# ArduinoUnoShield.net
KiCad netlist of a schematic drawn in Altium Designer
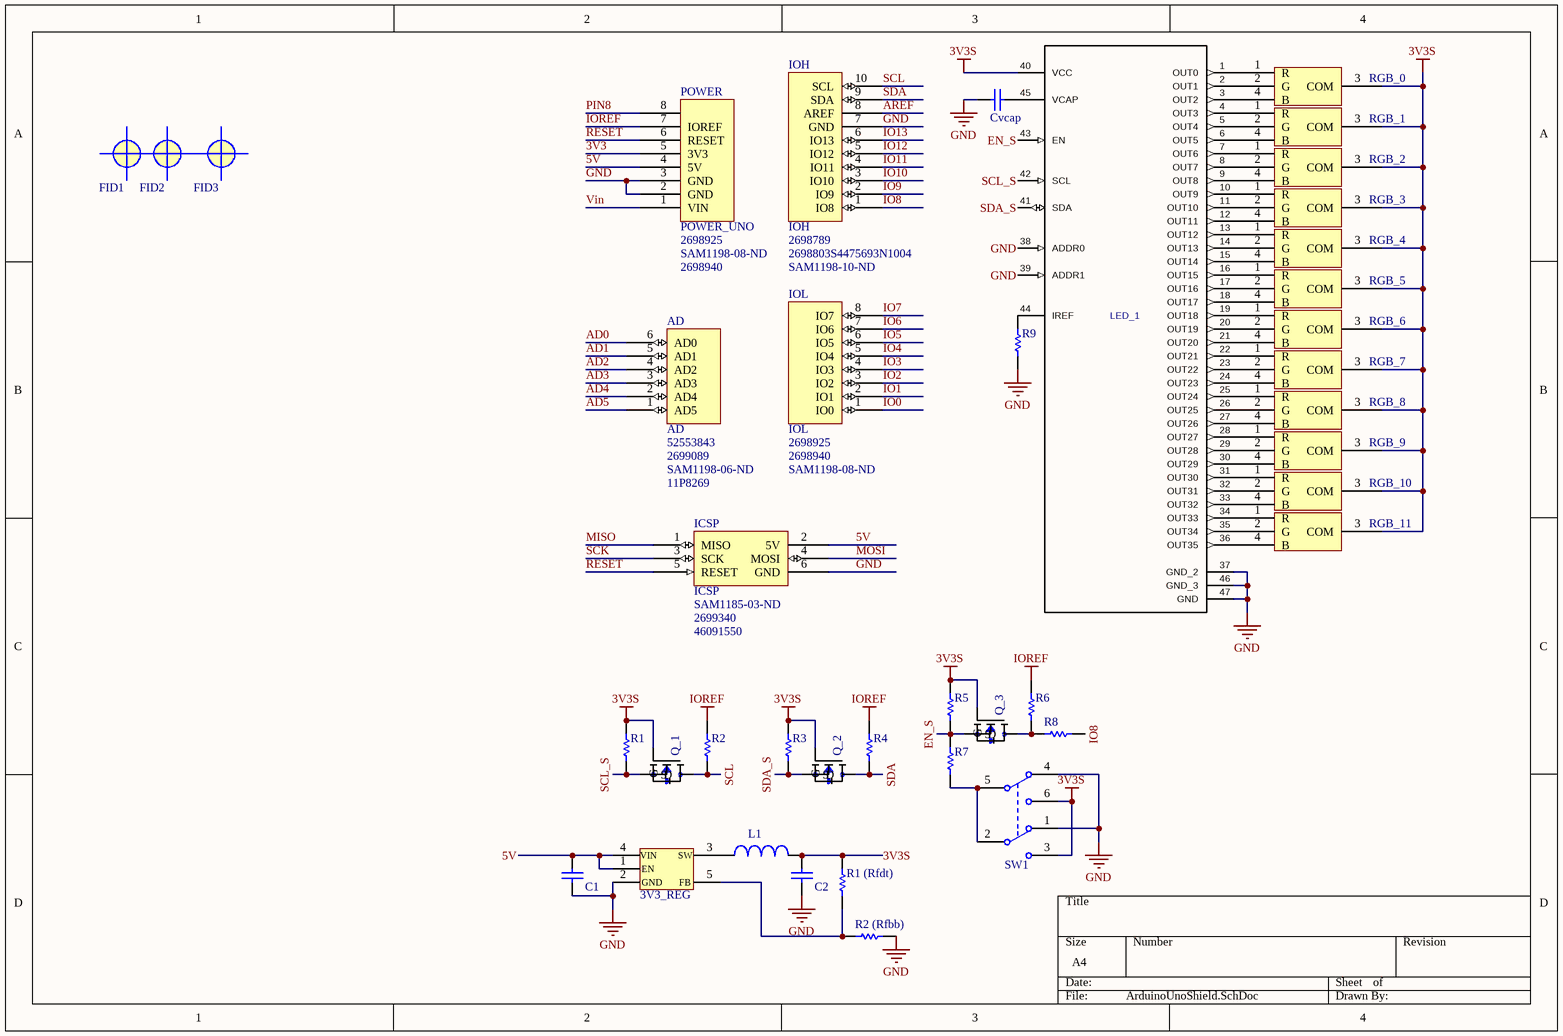
[diagram p0: ArduinoUnoShield.SchDoc]

(export (version "E")
  (design (tool "Eeschema 10.0.6"))
  (components
    (comp (ref "3V3_REG")
      (value "TLV62568DBVR")
      (footprint "*SOT95P280X145-5N")
      (libsource (lib "TLV62568DBVR") (part "TLV62568DBVR"))
    )
    (comp (ref "AD")
      (value "AD")
      (footprint "Header 6x1 8.5mm")
      (fields
        (field (name "SUPPLIER PART NUMBER 1") "52553843")
        (field (name "SUPPLIER PART NUMBER 2") "2699089")
        (field (name "SUPPLIER PART NUMBER 3") "SAM1198-06-ND")
        (field (name "SUPPLIER PART NUMBER 4") "11P8269")
      )
      (libsource (lib "Header") (part "AD"))
    )
    (comp (ref "C1")
      (value "4.7uF, 10%")
      (footprint "0805")
      (description "4.7uF, 10%, 10V")
      (fields (field (name "GFUPARTNO") "CL21A475KPFNNNE"))
      (libsource (lib "AltiumGFU64") (part "Cap"))
    )
    (comp (ref "C2")
      (value "1uF, 5%")
      (footprint "0805_CAP_HD")
      (description "1uF, 5%, 6.3V")
      (fields (field (name "GFUPARTNO") "08056D226MAT2A"))
      (libsource (lib "AltiumGFU64") (part "Cap"))
    )
    (comp (ref "Cvcap")
      (value "22uF, 20%")
      (footprint "0805_CAP_HD")
      (description "22uF, 20%, 6.3V")
      (fields (field (name "GFUPARTNO") "08056D226MAT2A"))
      (libsource (lib "AltiumGFU64") (part "Cap"))
    )
    (comp (ref "FID1")
      (value "FIDUCIAL")
      (footprint "FIDUCIAL (50MIL ROUND)")
      (description "FIDUCIAL (50MIL ROUND)")
      (libsource (lib "AltiumGFU64") (part "FIDUCIAL (ROUND)"))
    )
    (comp (ref "FID2")
      (value "FIDUCIAL")
      (footprint "FIDUCIAL (50MIL ROUND)")
      (description "FIDUCIAL (50MIL ROUND)")
      (libsource (lib "AltiumGFU64") (part "FIDUCIAL (ROUND)"))
    )
    (comp (ref "FID3")
      (value "FIDUCIAL")
      (footprint "FIDUCIAL (50MIL ROUND)")
      (description "FIDUCIAL (50MIL ROUND)")
      (libsource (lib "AltiumGFU64") (part "FIDUCIAL (ROUND)"))
    )
    (comp (ref "ICSP")
      (value "ICSP")
      (footprint "ICSP")
      (fields
        (field (name "SUPPLIER PART NUMBER 1") "SAM1185-03-ND")
        (field (name "SUPPLIER PART NUMBER 2") "2699340")
        (field (name "SUPPLIER PART NUMBER 3") "46091550")
      )
      (libsource (lib "Header") (part "ICSP"))
    )
    (comp (ref "IOH")
      (value "IOH")
      (footprint "Header 10x1 8.5mm")
      (fields
        (field (name "SUPPLIER PART NUMBER 1") "2698789")
        (field (name "SUPPLIER PART NUMBER 2") "2698803S4475693N1004")
        (field (name "SUPPLIER PART NUMBER 3") "SAM1198-10-ND")
      )
      (libsource (lib "Header") (part "IOH"))
    )
    (comp (ref "IOL")
      (value "IOL")
      (footprint "Header 8x1 8.5mm")
      (fields
        (field (name "SUPPLIER PART NUMBER 1") "2698925")
        (field (name "SUPPLIER PART NUMBER 2") "2698940")
        (field (name "SUPPLIER PART NUMBER 3") "SAM1198-08-ND")
      )
      (libsource (lib "Header") (part "IOL"))
    )
    (comp (ref "L1")
      (value "SDR0403-2R2ML")
      (footprint "*SDR0403")
      (description "2.2µH Unshielded Wirewound Inductor 2.6A 47mOhm Max Nonstandard")
      (fields (field (name "MF") "Bourns"))
      (libsource (lib "SDR0403-2R2ML") (part "SDR0403-2R2ML"))
    )
    (comp (ref "LED_1")
      (value "LP5036RJVR")
      (footprint "RJV0046A")
      (fields (field (name "MANUFACTURER") "Texas Instruments"))
      (libsource (lib "LP5036") (part "LP5036RJVR"))
    )
    (comp (ref "POWER")
      (value "POWER_UNO")
      (footprint "Header 8x1 8.5mm v2")
      (fields
        (field (name "SUPPLIER PART NUMBER 1") "2698925")
        (field (name "SUPPLIER PART NUMBER 2") "SAM1198-08-ND")
        (field (name "SUPPLIER PART NUMBER 3") "2698940")
      )
      (libsource (lib "Header") (part "POWER_UNO"))
    )
    (comp (ref "Q_1")
      (value "BSS138")
      (footprint "*BSS138_BSS138(Primary)")
      (description "N-Channel 50V 220mA _Ta_ 360mW _Ta_ Surface Mount Die")
      (fields (field (name "MF") "MICROSS/On Semiconductor"))
      (libsource (lib "BSS138") (part "BSS138"))
    )
    (comp (ref "Q_2")
      (value "BSS138")
      (footprint "*BSS138_BSS138(Primary)")
      (description "N-Channel 50V 220mA _Ta_ 360mW _Ta_ Surface Mount Die")
      (fields (field (name "MF") "MICROSS/On Semiconductor"))
      (libsource (lib "BSS138") (part "BSS138"))
    )
    (comp (ref "Q_3")
      (value "BSS138")
      (footprint "*BSS138_BSS138(Primary)")
      (description "N-Channel 50V 220mA _Ta_ 360mW _Ta_ Surface Mount Die")
      (fields (field (name "MF") "MICROSS/On Semiconductor"))
      (libsource (lib "BSS138") (part "BSS138"))
    )
    (comp (ref "R1")
      (value "4.7K, 5%")
      (footprint "0805")
      (description "RES 4.7K OHM 1/8W 5% 0805 SMD")
      (fields (field (name "GFUPARTNO") "RMCF0805JT4K70"))
      (libsource (lib "AltiumGFU64") (part "ResBasic"))
    )
    (comp (ref "R1 (Rfdt)")
      (value "R-NP")
      (footprint "0805_RES_HD")
      (description "NO PLACE RESISTOR")
      (fields (field (name "GFUPARTNO") "R-NP 0805"))
      (libsource (lib "AltiumGFU64") (part "ResBasic No Place"))
    )
    (comp (ref "R2")
      (value "4.7K, 5%")
      (footprint "0805")
      (description "RES 4.7K OHM 1/8W 5% 0805 SMD")
      (fields (field (name "GFUPARTNO") "RMCF0805JT4K70"))
      (libsource (lib "AltiumGFU64") (part "ResBasic"))
    )
    (comp (ref "R2 (Rfbb)")
      (value "R-NP")
      (footprint "0805_RES_HD")
      (description "NO PLACE RESISTOR")
      (fields (field (name "GFUPARTNO") "R-NP 0805"))
      (libsource (lib "AltiumGFU64") (part "ResBasic No Place"))
    )
    (comp (ref "R3")
      (value "4.7K, 5%")
      (footprint "0805")
      (description "RES 4.7K OHM 1/8W 5% 0805 SMD")
      (fields (field (name "GFUPARTNO") "RMCF0805JT4K70"))
      (libsource (lib "AltiumGFU64") (part "ResBasic"))
    )
    (comp (ref "R4")
      (value "4.7K, 5%")
      (footprint "0805")
      (description "RES 4.7K OHM 1/8W 5% 0805 SMD")
      (fields (field (name "GFUPARTNO") "RMCF0805JT4K70"))
      (libsource (lib "AltiumGFU64") (part "ResBasic"))
    )
    (comp (ref "R5")
      (value "4.7K, 5%")
      (footprint "0805")
      (description "RES 4.7K OHM 1/8W 5% 0805 SMD")
      (fields (field (name "GFUPARTNO") "RMCF0805JT4K70"))
      (libsource (lib "AltiumGFU64") (part "ResBasic"))
    )
    (comp (ref "R6")
      (value "4.7K, 5%")
      (footprint "0805")
      (description "RES 4.7K OHM 1/8W 5% 0805 SMD")
      (fields (field (name "GFUPARTNO") "RMCF0805JT4K70"))
      (libsource (lib "AltiumGFU64") (part "ResBasic"))
    )
    (comp (ref "R7")
      (value "0, 5%")
      (footprint "0603_RES_HD")
      (description "RES 0.0 OHM 1/10W 5% 0603 SMD")
      (fields (field (name "GFUPARTNO") "CRCW06030000Z0EA"))
      (libsource (lib "AltiumGFU64") (part "ResBasic"))
    )
    (comp (ref "R8")
      (value "0, 5%")
      (footprint "0603_RES_HD")
      (description "RES 0.0 OHM 1/10W 5% 0603 SMD")
      (fields (field (name "GFUPARTNO") "CRCW06030000Z0EA"))
      (libsource (lib "AltiumGFU64") (part "ResBasic"))
    )
    (comp (ref "R9")
      (value "4.7K, 5%")
      (footprint "0805")
      (description "RES 4.7K OHM 1/8W 5% 0805 SMD")
      (fields (field (name "GFUPARTNO") "RMCF0805JT4K70"))
      (libsource (lib "AltiumGFU64") (part "ResBasic"))
    )
    (comp (ref "RGB_0")
      (value "RGB LED")
      (footprint "PCBComponent_1")
      (libsource (lib "RGB_LED") (part "RGB LED"))
    )
    (comp (ref "RGB_1")
      (value "RGB LED")
      (footprint "PCBComponent_1")
      (libsource (lib "RGB_LED") (part "RGB LED"))
    )
    (comp (ref "RGB_2")
      (value "RGB LED")
      (footprint "PCBComponent_1")
      (libsource (lib "RGB_LED") (part "RGB LED"))
    )
    (comp (ref "RGB_3")
      (value "RGB LED")
      (footprint "PCBComponent_1")
      (libsource (lib "RGB_LED") (part "RGB LED"))
    )
    (comp (ref "RGB_4")
      (value "RGB LED")
      (footprint "PCBComponent_1")
      (libsource (lib "RGB_LED") (part "RGB LED"))
    )
    (comp (ref "RGB_5")
      (value "RGB LED")
      (footprint "PCBComponent_1")
      (libsource (lib "RGB_LED") (part "RGB LED"))
    )
    (comp (ref "RGB_6")
      (value "RGB LED")
      (footprint "PCBComponent_1")
      (libsource (lib "RGB_LED") (part "RGB LED"))
    )
    (comp (ref "RGB_7")
      (value "RGB LED")
      (footprint "PCBComponent_1")
      (libsource (lib "RGB_LED") (part "RGB LED"))
    )
    (comp (ref "RGB_8")
      (value "RGB LED")
      (footprint "PCBComponent_1")
      (libsource (lib "RGB_LED") (part "RGB LED"))
    )
    (comp (ref "RGB_9")
      (value "RGB LED")
      (footprint "PCBComponent_1")
      (libsource (lib "RGB_LED") (part "RGB LED"))
    )
    (comp (ref "RGB_10")
      (value "RGB LED")
      (footprint "PCBComponent_1")
      (libsource (lib "RGB_LED") (part "RGB LED"))
    )
    (comp (ref "RGB_11")
      (value "RGB LED")
      (footprint "PCBComponent_1")
      (libsource (lib "RGB_LED") (part "RGB LED"))
    )
    (comp (ref "SW1")
      (value "JS202011SCQN")
      (footprint "JS202011SCQN")
      (description "SWITCH SLIDE DPDT 6VDC 0.3A SMT")
      (libsource (lib "AltiumGFU64") (part "JS202011SCQN"))
    )
  )
  (nets
    (net (code "1") (name "/3V3") (class "Default")
      (node (ref "POWER") (pin "5") (pinfunction "3V3_5") (pintype "power_in"))
    )
    (net (code "2") (name "/5V") (class "Default")
      (node (ref "3V3_REG") (pin "1") (pinfunction "1_1") (pintype "passive"))
      (node (ref "3V3_REG") (pin "4") (pinfunction "4_4") (pintype "passive"))
      (node (ref "C1") (pin "2") (pinfunction "2_2") (pintype "passive"))
      (node (ref "ICSP") (pin "2") (pinfunction "5V_2") (pintype "power_in"))
      (node (ref "POWER") (pin "4") (pinfunction "5V_4") (pintype "power_in"))
    )
    (net (code "3") (name "/AD0") (class "Default")
      (node (ref "AD") (pin "6") (pinfunction "AD0_6") (pintype "bidirectional"))
    )
    (net (code "4") (name "/AD1") (class "Default")
      (node (ref "AD") (pin "5") (pinfunction "AD1_5") (pintype "bidirectional"))
    )
    (net (code "5") (name "/AD2") (class "Default")
      (node (ref "AD") (pin "4") (pinfunction "AD2_4") (pintype "bidirectional"))
    )
    (net (code "6") (name "/AD3") (class "Default")
      (node (ref "AD") (pin "3") (pinfunction "AD3_3") (pintype "bidirectional"))
    )
    (net (code "7") (name "/AD4") (class "Default")
      (node (ref "AD") (pin "2") (pinfunction "AD4_2") (pintype "bidirectional"))
    )
    (net (code "8") (name "/AD5") (class "Default")
      (node (ref "AD") (pin "1") (pinfunction "AD5_1") (pintype "bidirectional"))
    )
    (net (code "9") (name "/AREF") (class "Default")
      (node (ref "IOH") (pin "8") (pinfunction "AREF_8") (pintype "passive"))
    )
    (net (code "10") (name "/EN_S") (class "Default")
      (node (ref "LED_1") (pin "43") (pinfunction "EN_43") (pintype "input"))
      (node (ref "Q_3") (pin "S") (pinfunction "S_S") (pintype "passive"))
      (node (ref "R5") (pin "1") (pinfunction "1_1") (pintype "passive"))
      (node (ref "R7") (pin "2") (pinfunction "2_2") (pintype "passive"))
    )
    (net (code "11") (name "/IO0") (class "Default")
      (node (ref "IOL") (pin "1") (pinfunction "IO0_1") (pintype "bidirectional"))
    )
    (net (code "12") (name "/IO1") (class "Default")
      (node (ref "IOL") (pin "2") (pinfunction "IO1_2") (pintype "bidirectional"))
    )
    (net (code "13") (name "/IO2") (class "Default")
      (node (ref "IOL") (pin "3") (pinfunction "IO2_3") (pintype "bidirectional"))
    )
    (net (code "14") (name "/IO3") (class "Default")
      (node (ref "IOL") (pin "4") (pinfunction "IO3_4") (pintype "bidirectional"))
    )
    (net (code "15") (name "/IO4") (class "Default")
      (node (ref "IOL") (pin "5") (pinfunction "IO4_5") (pintype "bidirectional"))
    )
    (net (code "16") (name "/IO5") (class "Default")
      (node (ref "IOL") (pin "6") (pinfunction "IO5_6") (pintype "bidirectional"))
    )
    (net (code "17") (name "/IO6") (class "Default")
      (node (ref "IOL") (pin "7") (pinfunction "IO6_7") (pintype "bidirectional"))
    )
    (net (code "18") (name "/IO7") (class "Default")
      (node (ref "IOL") (pin "8") (pinfunction "IO7_8") (pintype "bidirectional"))
    )
    (net (code "19") (name "/IO8") (class "Default")
      (node (ref "IOH") (pin "1") (pinfunction "IO8_1") (pintype "bidirectional"))
      (node (ref "R8") (pin "1") (pinfunction "1_1") (pintype "passive"))
    )
    (net (code "20") (name "/IO9") (class "Default")
      (node (ref "IOH") (pin "2") (pinfunction "IO9_2") (pintype "bidirectional"))
    )
    (net (code "21") (name "/IO10") (class "Default")
      (node (ref "IOH") (pin "3") (pinfunction "IO10_3") (pintype "bidirectional"))
    )
    (net (code "22") (name "/IO11") (class "Default")
      (node (ref "IOH") (pin "4") (pinfunction "IO11_4") (pintype "bidirectional"))
    )
    (net (code "23") (name "/IO12") (class "Default")
      (node (ref "IOH") (pin "5") (pinfunction "IO12_5") (pintype "bidirectional"))
    )
    (net (code "24") (name "/IO13") (class "Default")
      (node (ref "IOH") (pin "6") (pinfunction "IO13_6") (pintype "bidirectional"))
    )
    (net (code "25") (name "/MISO") (class "Default")
      (node (ref "ICSP") (pin "1") (pinfunction "MISO_1") (pintype "bidirectional"))
    )
    (net (code "26") (name "/MOSI") (class "Default")
      (node (ref "ICSP") (pin "4") (pinfunction "MOSI_4") (pintype "bidirectional"))
    )
    (net (code "27") (name "/PIN8") (class "Default") (node (ref "POWER") (pin "8") (pintype "passive")))
    (net (code "28") (name "/RESET") (class "Default")
      (node (ref "ICSP") (pin "5") (pinfunction "RESET_5") (pintype "input"))
      (node (ref "POWER") (pin "6") (pinfunction "RESET_6") (pintype "passive"))
    )
    (net (code "29") (name "/SCK") (class "Default")
      (node (ref "ICSP") (pin "3") (pinfunction "SCK_3") (pintype "bidirectional"))
    )
    (net (code "30") (name "/SCL") (class "Default")
      (node (ref "IOH") (pin "10") (pinfunction "SCL_10") (pintype "bidirectional"))
      (node (ref "Q_1") (pin "D") (pinfunction "D_D") (pintype "passive"))
      (node (ref "R2") (pin "1") (pinfunction "1_1") (pintype "passive"))
    )
    (net (code "31") (name "/SCL_S") (class "Default")
      (node (ref "LED_1") (pin "42") (pinfunction "SCL_42") (pintype "input"))
      (node (ref "Q_1") (pin "S") (pinfunction "S_S") (pintype "passive"))
      (node (ref "R1") (pin "1") (pinfunction "1_1") (pintype "passive"))
    )
    (net (code "32") (name "/SDA") (class "Default")
      (node (ref "IOH") (pin "9") (pinfunction "SDA_9") (pintype "bidirectional"))
      (node (ref "Q_2") (pin "D") (pinfunction "D_D") (pintype "passive"))
      (node (ref "R4") (pin "1") (pinfunction "1_1") (pintype "passive"))
    )
    (net (code "33") (name "/SDA_S") (class "Default")
      (node (ref "LED_1") (pin "41") (pinfunction "SDA_41") (pintype "bidirectional"))
      (node (ref "Q_2") (pin "S") (pinfunction "S_S") (pintype "passive"))
      (node (ref "R3") (pin "1") (pinfunction "1_1") (pintype "passive"))
    )
    (net (code "34") (name "/Vin") (class "Default")
      (node (ref "POWER") (pin "1") (pinfunction "VIN_1") (pintype "power_in"))
    )
    (net (code "35") (name "3V3S") (class "Default")
      (node (ref "C2") (pin "2") (pinfunction "2_2") (pintype "passive"))
      (node (ref "L1") (pin "2") (pinfunction "2_2") (pintype "passive"))
      (node (ref "LED_1") (pin "40") (pinfunction "VCC_40") (pintype "power_in"))
      (node (ref "Q_1") (pin "G") (pinfunction "G_G") (pintype "passive"))
      (node (ref "Q_2") (pin "G") (pinfunction "G_G") (pintype "passive"))
      (node (ref "Q_3") (pin "G") (pinfunction "G_G") (pintype "passive"))
      (node (ref "R1") (pin "2") (pinfunction "2_2") (pintype "passive"))
      (node (ref "R1 (Rfdt)") (pin "2") (pinfunction "2_2") (pintype "passive"))
      (node (ref "R3") (pin "2") (pinfunction "2_2") (pintype "passive"))
      (node (ref "R5") (pin "2") (pinfunction "2_2") (pintype "passive"))
      (node (ref "RGB_0") (pin "3") (pinfunction "COM_3") (pintype "passive"))
      (node (ref "RGB_1") (pin "3") (pinfunction "COM_3") (pintype "passive"))
      (node (ref "RGB_10") (pin "3") (pinfunction "COM_3") (pintype "passive"))
      (node (ref "RGB_11") (pin "3") (pinfunction "COM_3") (pintype "passive"))
      (node (ref "RGB_2") (pin "3") (pinfunction "COM_3") (pintype "passive"))
      (node (ref "RGB_3") (pin "3") (pinfunction "COM_3") (pintype "passive"))
      (node (ref "RGB_4") (pin "3") (pinfunction "COM_3") (pintype "passive"))
      (node (ref "RGB_5") (pin "3") (pinfunction "COM_3") (pintype "passive"))
      (node (ref "RGB_6") (pin "3") (pinfunction "COM_3") (pintype "passive"))
      (node (ref "RGB_7") (pin "3") (pinfunction "COM_3") (pintype "passive"))
      (node (ref "RGB_8") (pin "3") (pinfunction "COM_3") (pintype "passive"))
      (node (ref "RGB_9") (pin "3") (pinfunction "COM_3") (pintype "passive"))
      (node (ref "SW1") (pin "3") (pinfunction "NO2_3") (pintype "passive"))
      (node (ref "SW1") (pin "6") (pinfunction "NC1_6") (pintype "passive"))
    )
    (net (code "36") (name "GND") (class "Default")
      (node (ref "3V3_REG") (pin "2") (pinfunction "2_2") (pintype "passive"))
      (node (ref "C1") (pin "1") (pinfunction "1_1") (pintype "passive"))
      (node (ref "C2") (pin "1") (pinfunction "1_1") (pintype "passive"))
      (node (ref "Cvcap") (pin "2") (pinfunction "2_2") (pintype "passive"))
      (node (ref "ICSP") (pin "6") (pinfunction "GND_6") (pintype "power_in"))
      (node (ref "IOH") (pin "7") (pinfunction "GND_7") (pintype "power_in"))
      (node (ref "LED_1") (pin "37") (pinfunction "GND_2_37") (pintype "power_in"))
      (node (ref "LED_1") (pin "38") (pinfunction "ADDR0_38") (pintype "input"))
      (node (ref "LED_1") (pin "39") (pinfunction "ADDR1_39") (pintype "input"))
      (node (ref "LED_1") (pin "46") (pinfunction "GND_3_46") (pintype "power_in"))
      (node (ref "LED_1") (pin "47") (pinfunction "GND_47") (pintype "power_in"))
      (node (ref "POWER") (pin "2") (pinfunction "GND_2") (pintype "power_in"))
      (node (ref "POWER") (pin "3") (pinfunction "GND_3") (pintype "power_in"))
      (node (ref "R2 (Rfbb)") (pin "2") (pinfunction "2_2") (pintype "passive"))
      (node (ref "R9") (pin "1") (pinfunction "1_1") (pintype "passive"))
      (node (ref "SW1") (pin "1") (pinfunction "NC2_1") (pintype "passive"))
      (node (ref "SW1") (pin "4") (pinfunction "NO1_4") (pintype "passive"))
    )
    (net (code "37") (name "IOREF") (class "Default")
      (node (ref "POWER") (pin "7") (pinfunction "IOREF_7") (pintype "power_in"))
      (node (ref "R2") (pin "2") (pinfunction "2_2") (pintype "passive"))
      (node (ref "R4") (pin "2") (pinfunction "2_2") (pintype "passive"))
      (node (ref "R6") (pin "2") (pinfunction "2_2") (pintype "passive"))
    )
    (net (code "38") (name "Net-(3V3_REG-Pad3)") (class "Default")
      (node (ref "3V3_REG") (pin "3") (pinfunction "3_3") (pintype "passive"))
      (node (ref "L1") (pin "1") (pinfunction "1_1") (pintype "passive"))
    )
    (net (code "39") (name "Net-(3V3_REG-Pad5)") (class "Default")
      (node (ref "3V3_REG") (pin "5") (pinfunction "5_5") (pintype "passive"))
      (node (ref "R1 (Rfdt)") (pin "1") (pinfunction "1_1") (pintype "passive"))
      (node (ref "R2 (Rfbb)") (pin "1") (pinfunction "1_1") (pintype "passive"))
    )
    (net (code "40") (name "Net-(LED_1-IREF)") (class "Default")
      (node (ref "LED_1") (pin "44") (pinfunction "IREF_44") (pintype "passive"))
      (node (ref "R9") (pin "2") (pinfunction "2_2") (pintype "passive"))
    )
    (net (code "41") (name "Net-(LED_1-OUT0)") (class "Default")
      (node (ref "LED_1") (pin "1") (pinfunction "OUT0_1") (pintype "output"))
      (node (ref "RGB_0") (pin "1") (pinfunction "R_1") (pintype "passive"))
    )
    (net (code "42") (name "Net-(LED_1-OUT1)") (class "Default")
      (node (ref "LED_1") (pin "2") (pinfunction "OUT1_2") (pintype "output"))
      (node (ref "RGB_0") (pin "2") (pinfunction "G_2") (pintype "passive"))
    )
    (net (code "43") (name "Net-(LED_1-OUT2)") (class "Default")
      (node (ref "LED_1") (pin "3") (pinfunction "OUT2_3") (pintype "output"))
      (node (ref "RGB_0") (pin "4") (pinfunction "B_4") (pintype "passive"))
    )
    (net (code "44") (name "Net-(LED_1-OUT3)") (class "Default")
      (node (ref "LED_1") (pin "4") (pinfunction "OUT3_4") (pintype "output"))
      (node (ref "RGB_1") (pin "1") (pinfunction "R_1") (pintype "passive"))
    )
    (net (code "45") (name "Net-(LED_1-OUT4)") (class "Default")
      (node (ref "LED_1") (pin "5") (pinfunction "OUT4_5") (pintype "output"))
      (node (ref "RGB_1") (pin "2") (pinfunction "G_2") (pintype "passive"))
    )
    (net (code "46") (name "Net-(LED_1-OUT5)") (class "Default")
      (node (ref "LED_1") (pin "6") (pinfunction "OUT5_6") (pintype "output"))
      (node (ref "RGB_1") (pin "4") (pinfunction "B_4") (pintype "passive"))
    )
    (net (code "47") (name "Net-(LED_1-OUT6)") (class "Default")
      (node (ref "LED_1") (pin "7") (pinfunction "OUT6_7") (pintype "output"))
      (node (ref "RGB_2") (pin "1") (pinfunction "R_1") (pintype "passive"))
    )
    (net (code "48") (name "Net-(LED_1-OUT7)") (class "Default")
      (node (ref "LED_1") (pin "8") (pinfunction "OUT7_8") (pintype "output"))
      (node (ref "RGB_2") (pin "2") (pinfunction "G_2") (pintype "passive"))
    )
    (net (code "49") (name "Net-(LED_1-OUT8)") (class "Default")
      (node (ref "LED_1") (pin "9") (pinfunction "OUT8_9") (pintype "output"))
      (node (ref "RGB_2") (pin "4") (pinfunction "B_4") (pintype "passive"))
    )
    (net (code "50") (name "Net-(LED_1-OUT9)") (class "Default")
      (node (ref "LED_1") (pin "10") (pinfunction "OUT9_10") (pintype "output"))
      (node (ref "RGB_3") (pin "1") (pinfunction "R_1") (pintype "passive"))
    )
    (net (code "51") (name "Net-(LED_1-OUT10)") (class "Default")
      (node (ref "LED_1") (pin "11") (pinfunction "OUT10_11") (pintype "output"))
      (node (ref "RGB_3") (pin "2") (pinfunction "G_2") (pintype "passive"))
    )
    (net (code "52") (name "Net-(LED_1-OUT11)") (class "Default")
      (node (ref "LED_1") (pin "12") (pinfunction "OUT11_12") (pintype "output"))
      (node (ref "RGB_3") (pin "4") (pinfunction "B_4") (pintype "passive"))
    )
    (net (code "53") (name "Net-(LED_1-OUT12)") (class "Default")
      (node (ref "LED_1") (pin "13") (pinfunction "OUT12_13") (pintype "output"))
      (node (ref "RGB_4") (pin "1") (pinfunction "R_1") (pintype "passive"))
    )
    (net (code "54") (name "Net-(LED_1-OUT13)") (class "Default")
      (node (ref "LED_1") (pin "14") (pinfunction "OUT13_14") (pintype "output"))
      (node (ref "RGB_4") (pin "2") (pinfunction "G_2") (pintype "passive"))
    )
    (net (code "55") (name "Net-(LED_1-OUT14)") (class "Default")
      (node (ref "LED_1") (pin "15") (pinfunction "OUT14_15") (pintype "output"))
      (node (ref "RGB_4") (pin "4") (pinfunction "B_4") (pintype "passive"))
    )
    (net (code "56") (name "Net-(LED_1-OUT15)") (class "Default")
      (node (ref "LED_1") (pin "16") (pinfunction "OUT15_16") (pintype "output"))
      (node (ref "RGB_5") (pin "1") (pinfunction "R_1") (pintype "passive"))
    )
    (net (code "57") (name "Net-(LED_1-OUT16)") (class "Default")
      (node (ref "LED_1") (pin "17") (pinfunction "OUT16_17") (pintype "output"))
      (node (ref "RGB_5") (pin "2") (pinfunction "G_2") (pintype "passive"))
    )
    (net (code "58") (name "Net-(LED_1-OUT17)") (class "Default")
      (node (ref "LED_1") (pin "18") (pinfunction "OUT17_18") (pintype "output"))
      (node (ref "RGB_5") (pin "4") (pinfunction "B_4") (pintype "passive"))
    )
    (net (code "59") (name "Net-(LED_1-OUT18)") (class "Default")
      (node (ref "LED_1") (pin "19") (pinfunction "OUT18_19") (pintype "output"))
      (node (ref "RGB_6") (pin "1") (pinfunction "R_1") (pintype "passive"))
    )
    (net (code "60") (name "Net-(LED_1-OUT19)") (class "Default")
      (node (ref "LED_1") (pin "20") (pinfunction "OUT19_20") (pintype "output"))
      (node (ref "RGB_6") (pin "2") (pinfunction "G_2") (pintype "passive"))
    )
    (net (code "61") (name "Net-(LED_1-OUT20)") (class "Default")
      (node (ref "LED_1") (pin "21") (pinfunction "OUT20_21") (pintype "output"))
      (node (ref "RGB_6") (pin "4") (pinfunction "B_4") (pintype "passive"))
    )
    (net (code "62") (name "Net-(LED_1-OUT21)") (class "Default")
      (node (ref "LED_1") (pin "22") (pinfunction "OUT21_22") (pintype "output"))
      (node (ref "RGB_7") (pin "1") (pinfunction "R_1") (pintype "passive"))
    )
    (net (code "63") (name "Net-(LED_1-OUT22)") (class "Default")
      (node (ref "LED_1") (pin "23") (pinfunction "OUT22_23") (pintype "output"))
      (node (ref "RGB_7") (pin "2") (pinfunction "G_2") (pintype "passive"))
    )
    (net (code "64") (name "Net-(LED_1-OUT23)") (class "Default")
      (node (ref "LED_1") (pin "24") (pinfunction "OUT23_24") (pintype "output"))
      (node (ref "RGB_7") (pin "4") (pinfunction "B_4") (pintype "passive"))
    )
    (net (code "65") (name "Net-(LED_1-OUT24)") (class "Default")
      (node (ref "LED_1") (pin "25") (pinfunction "OUT24_25") (pintype "output"))
      (node (ref "RGB_8") (pin "1") (pinfunction "R_1") (pintype "passive"))
    )
    (net (code "66") (name "Net-(LED_1-OUT25)") (class "Default")
      (node (ref "LED_1") (pin "26") (pinfunction "OUT25_26") (pintype "output"))
      (node (ref "RGB_8") (pin "2") (pinfunction "G_2") (pintype "passive"))
    )
    (net (code "67") (name "Net-(LED_1-OUT26)") (class "Default")
      (node (ref "LED_1") (pin "27") (pinfunction "OUT26_27") (pintype "output"))
      (node (ref "RGB_8") (pin "4") (pinfunction "B_4") (pintype "passive"))
    )
    (net (code "68") (name "Net-(LED_1-OUT27)") (class "Default")
      (node (ref "LED_1") (pin "28") (pinfunction "OUT27_28") (pintype "output"))
      (node (ref "RGB_9") (pin "1") (pinfunction "R_1") (pintype "passive"))
    )
    (net (code "69") (name "Net-(LED_1-OUT28)") (class "Default")
      (node (ref "LED_1") (pin "29") (pinfunction "OUT28_29") (pintype "output"))
      (node (ref "RGB_9") (pin "2") (pinfunction "G_2") (pintype "passive"))
    )
    (net (code "70") (name "Net-(LED_1-OUT29)") (class "Default")
      (node (ref "LED_1") (pin "30") (pinfunction "OUT29_30") (pintype "output"))
      (node (ref "RGB_9") (pin "4") (pinfunction "B_4") (pintype "passive"))
    )
    (net (code "71") (name "Net-(LED_1-OUT30)") (class "Default")
      (node (ref "LED_1") (pin "31") (pinfunction "OUT30_31") (pintype "output"))
      (node (ref "RGB_10") (pin "1") (pinfunction "R_1") (pintype "passive"))
    )
    (net (code "72") (name "Net-(LED_1-OUT31)") (class "Default")
      (node (ref "LED_1") (pin "32") (pinfunction "OUT31_32") (pintype "output"))
      (node (ref "RGB_10") (pin "2") (pinfunction "G_2") (pintype "passive"))
    )
    (net (code "73") (name "Net-(LED_1-OUT32)") (class "Default")
      (node (ref "LED_1") (pin "33") (pinfunction "OUT32_33") (pintype "output"))
      (node (ref "RGB_10") (pin "4") (pinfunction "B_4") (pintype "passive"))
    )
    (net (code "74") (name "Net-(LED_1-OUT33)") (class "Default")
      (node (ref "LED_1") (pin "34") (pinfunction "OUT33_34") (pintype "output"))
      (node (ref "RGB_11") (pin "1") (pinfunction "R_1") (pintype "passive"))
    )
    (net (code "75") (name "Net-(LED_1-OUT34)") (class "Default")
      (node (ref "LED_1") (pin "35") (pinfunction "OUT34_35") (pintype "output"))
      (node (ref "RGB_11") (pin "2") (pinfunction "G_2") (pintype "passive"))
    )
    (net (code "76") (name "Net-(LED_1-OUT35)") (class "Default")
      (node (ref "LED_1") (pin "36") (pinfunction "OUT35_36") (pintype "output"))
      (node (ref "RGB_11") (pin "4") (pinfunction "B_4") (pintype "passive"))
    )
    (net (code "77") (name "Net-(LED_1-VCAP)") (class "Default")
      (node (ref "Cvcap") (pin "1") (pinfunction "1_1") (pintype "passive"))
      (node (ref "LED_1") (pin "45") (pinfunction "VCAP_45") (pintype "power_in"))
    )
    (net (code "78") (name "Net-(Q_3-PadD)") (class "Default")
      (node (ref "Q_3") (pin "D") (pinfunction "D_D") (pintype "passive"))
      (node (ref "R6") (pin "1") (pinfunction "1_1") (pintype "passive"))
      (node (ref "R8") (pin "2") (pinfunction "2_2") (pintype "passive"))
    )
    (net (code "79") (name "Net-(SW1-COMMON1)") (class "Default")
      (node (ref "R7") (pin "1") (pinfunction "1_1") (pintype "passive"))
      (node (ref "SW1") (pin "2") (pinfunction "COMMON1_2") (pintype "passive"))
      (node (ref "SW1") (pin "5") (pinfunction "COMMON2_5") (pintype "passive"))
    )
  )
)
